# ADC.net
KiCad netlist of a schematic drawn in Altium Designer
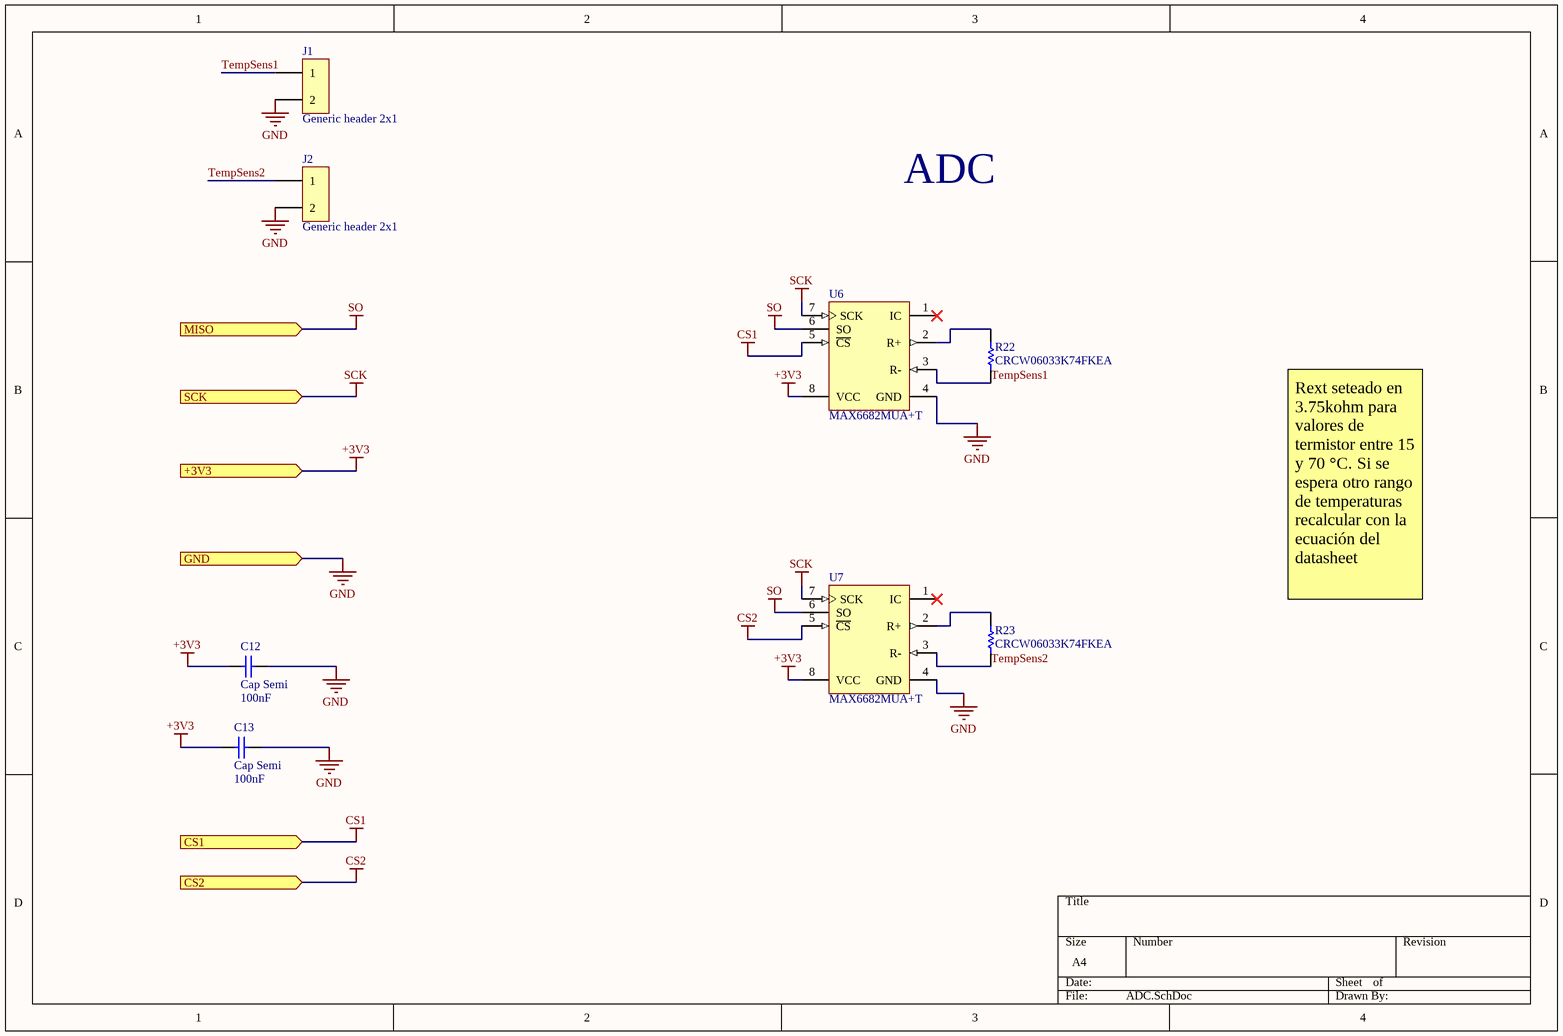
[diagram p0: ADC.SchDoc]

(export (version "E")
  (design (tool "Eeschema 10.0.6"))
  (components
    (comp (ref "C12")
      (value "Cap Semi")
      (footprint "1608[0603]")
      (description "Capacitor (Semiconductor SIM Model)")
      (fields
        (field (name "ALTIUM_VALUE") "100nF")
        (field (name "MANUFACTURER") "Taiyo Yuden")
        (field (name "MANUFACTURER PART NUMBER") "UMK107B104KAHT")
        (field (name "PUBLISHER") "Altium Limited")
      )
      (libsource (lib "Miscellaneous Devices") (part "Cap Semi"))
    )
    (comp (ref "C13")
      (value "Cap Semi")
      (footprint "1608[0603]")
      (description "Capacitor (Semiconductor SIM Model)")
      (fields
        (field (name "ALTIUM_VALUE") "100nF")
        (field (name "MANUFACTURER") "Taiyo Yuden")
        (field (name "MANUFACTURER PART NUMBER") "UMK107B104KAHT")
        (field (name "PUBLISHER") "Altium Limited")
      )
      (libsource (lib "Miscellaneous Devices") (part "Cap Semi"))
    )
    (comp (ref "J1")
      (value "Generic header 2x1")
      (footprint "JST-2x1")
      (description "Generic Header 2pos, 1 row, 2.54 pitch")
      (fields
        (field (name "MANUFACTURER") "CJT(Changjiang Connectors)")
        (field (name "MANUFACTURER PART NUMBER") "A2547WV-2P")
      )
      (libsource (lib "IoWLabsConnectors") (part "Header - 2x1"))
    )
    (comp (ref "J2")
      (value "Generic header 2x1")
      (footprint "JST-2x1")
      (description "Generic Header 2pos, 1 row, 2.54 pitch")
      (fields
        (field (name "MANUFACTURER") "CJT(Changjiang Connectors)")
        (field (name "MANUFACTURER PART NUMBER") "A2547WV-2P")
      )
      (libsource (lib "IoWLabsConnectors") (part "Header - 2x1"))
    )
    (comp (ref "R22")
      (value "CRCW06033K74FKEA")
      (footprint "RESC1609X50X30LL10T20")
      (description "4.22kΩ ±1% ±100ppm/℃ 0.1W 0603 Chip Resistor - Surface Mount ROHS")
      (fields (field (name "MANUFACTURER") "Vishay Dale"))
      (libsource (lib "Altium Content Vault") (part "RES"))
    )
    (comp (ref "R23")
      (value "CRCW06033K74FKEA")
      (footprint "RESC1609X50X30LL10T20")
      (description "4.22kΩ ±1% ±100ppm/℃ 0.1W 0603 Chip Resistor - Surface Mount ROHS")
      (fields (field (name "MANUFACTURER") "Vishay Dale"))
      (libsource (lib "Altium Content Vault") (part "RES"))
    )
    (comp (ref "U6")
      (value "MAX6682MUA+T")
      (footprint "MAXM-U8+1_L")
      (fields (field (name "GENERIC PART NUMBER") "MAX6682"))
      (libsource (lib "Altium Content Vault") (part "MAX6682-U8X1"))
    )
    (comp (ref "U7")
      (value "MAX6682MUA+T")
      (footprint "MAXM-U8+1_L")
      (fields (field (name "GENERIC PART NUMBER") "MAX6682"))
      (libsource (lib "Altium Content Vault") (part "MAX6682-U8X1"))
    )
  )
  (nets
    (net (code "1") (name "+3V3") (class "Default")
      (node (ref "C12") (pin "2") (pinfunction "2_2") (pintype "passive"))
      (node (ref "C13") (pin "2") (pinfunction "2_2") (pintype "passive"))
      (node (ref "U6") (pin "8") (pinfunction "VCC_8") (pintype "power_in"))
      (node (ref "U7") (pin "8") (pinfunction "VCC_8") (pintype "power_in"))
    )
    (net (code "2") (name "/TempSens1") (class "Default")
      (node (ref "J1") (pin "1") (pinfunction "1_1") (pintype "passive"))
      (node (ref "R22") (pin "1") (pinfunction "1_1") (pintype "passive"))
      (node (ref "U6") (pin "3") (pinfunction "R-_3") (pintype "input"))
    )
    (net (code "3") (name "/TempSens2") (class "Default")
      (node (ref "J2") (pin "1") (pinfunction "1_1") (pintype "passive"))
      (node (ref "R23") (pin "1") (pinfunction "1_1") (pintype "passive"))
      (node (ref "U7") (pin "3") (pinfunction "R-_3") (pintype "input"))
    )
    (net (code "4") (name "CS1") (class "Default")
      (node (ref "U6") (pin "5") (pinfunction "~{CS}_5") (pintype "input"))
    )
    (net (code "5") (name "CS2") (class "Default")
      (node (ref "U7") (pin "5") (pinfunction "~{CS}_5") (pintype "input"))
    )
    (net (code "6") (name "GND") (class "Default")
      (node (ref "C12") (pin "1") (pinfunction "1_1") (pintype "passive"))
      (node (ref "C13") (pin "1") (pinfunction "1_1") (pintype "passive"))
      (node (ref "J1") (pin "2") (pinfunction "2_2") (pintype "passive"))
      (node (ref "J2") (pin "2") (pinfunction "2_2") (pintype "passive"))
      (node (ref "U6") (pin "4") (pinfunction "GND_4") (pintype "power_in"))
      (node (ref "U7") (pin "4") (pinfunction "GND_4") (pintype "power_in"))
    )
    (net (code "7") (name "Net-(U6-R+)") (class "Default")
      (node (ref "R22") (pin "2") (pinfunction "2_2") (pintype "passive"))
      (node (ref "U6") (pin "2") (pinfunction "R+_2") (pintype "output"))
    )
    (net (code "8") (name "Net-(U7-R+)") (class "Default")
      (node (ref "R23") (pin "2") (pinfunction "2_2") (pintype "passive"))
      (node (ref "U7") (pin "2") (pinfunction "R+_2") (pintype "output"))
    )
    (net (code "9") (name "SCK") (class "Default")
      (node (ref "U6") (pin "7") (pinfunction "SCK_7") (pintype "input"))
      (node (ref "U7") (pin "7") (pinfunction "SCK_7") (pintype "input"))
    )
    (net (code "10") (name "SO") (class "Default")
      (node (ref "U6") (pin "6") (pinfunction "SO_6") (pintype "tri_state"))
      (node (ref "U7") (pin "6") (pinfunction "SO_6") (pintype "tri_state"))
    )
    (net (code "11") (name "unconnected-(U6-IC-Pad1)") (class "Default")
      (node (ref "U6") (pin "1") (pinfunction "IC_1") (pintype "passive+no_connect"))
    )
    (net (code "12") (name "unconnected-(U7-IC-Pad1)") (class "Default")
      (node (ref "U7") (pin "1") (pinfunction "IC_1") (pintype "passive+no_connect"))
    )
  )
)
